# Camera.net
KiCad netlist of a schematic drawn in Altium Designer
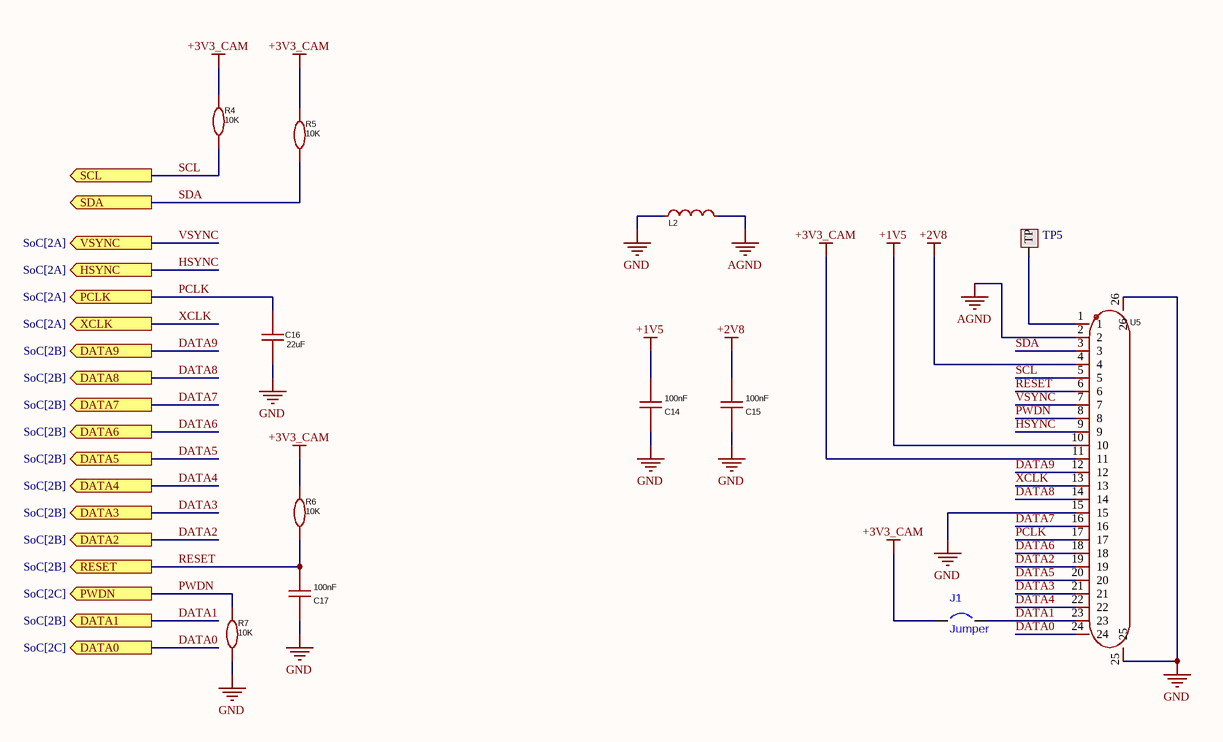
[diagram p0: Camera.SchDoc]

(export (version "E")
  (design (tool "Eeschema 10.0.6"))
  (components
    (comp (ref "C14")
      (value "100nF")
      (footprint "100nF SMD Ceramic 201")
      (description "10V 100nF X5R ±10% 0201 Multilayer Ceramic Capacitors MLCC - SMD/SMT ROHS")
      (fields
        (field (name "MANUFACTURER") "muRata(村田)")
        (field (name "MANUFACTURER PART") "GRM033R61A104KE84D")
      )
      (libsource (lib "Esp32 CAM SCH") (part "100nF SMD Ceramic 201"))
    )
    (comp (ref "C15")
      (value "100nF")
      (footprint "100nF SMD Ceramic 201")
      (description "10V 100nF X5R ±10% 0201 Multilayer Ceramic Capacitors MLCC - SMD/SMT ROHS")
      (fields
        (field (name "MANUFACTURER") "muRata(村田)")
        (field (name "MANUFACTURER PART") "GRM033R61A104KE84D")
      )
      (libsource (lib "Esp32 CAM SCH") (part "100nF SMD Ceramic 201"))
    )
    (comp (ref "C16")
      (value "22uF")
      (footprint "22uF SMD Ceramic 1210")
      (description "10V 22uF X7R ±10% 1210 Multilayer Ceramic Capacitors MLCC - SMD/SMT ROHS")
      (fields
        (field (name "MANUFACTURER") "KEMET(基美)")
        (field (name "MANUFACTURER PART") "C1210C226K8RACAUTO")
      )
      (libsource (lib "Esp32 CAM SCH") (part "22uF SMD Ceramic 1210"))
    )
    (comp (ref "C17")
      (value "100nF")
      (footprint "100nF SMD Ceramic 201")
      (description "10V 100nF X5R ±10% 0201 Multilayer Ceramic Capacitors MLCC - SMD/SMT ROHS")
      (fields
        (field (name "MANUFACTURER") "muRata(村田)")
        (field (name "MANUFACTURER PART") "GRM033R61A104KE84D")
      )
      (libsource (lib "Esp32 CAM SCH") (part "100nF SMD Ceramic 201"))
    )
    (comp (ref "J1")
      (value "Jumper")
      (footprint "PAD-JUMPER-2")
      (description "SMD JUMPER")
      (libsource (lib "Esp32 CAM SCH") (part "JUMPER SOLDER BRIDGE"))
    )
    (comp (ref "L2")
      (value "BLM15AG601SN1D")
      (footprint "Ferrite")
      (description "520mΩ ±25% 600Ω@100MHz 0402 Ferrite Beads ROHS")
      (fields (field (name "MANUFACTURER") "muRata(村田)") (field (name "TOLERANCE") "±25%"))
      (libsource (lib "Esp32 CAM SCH") (part "BLM15AG601SN1D"))
    )
    (comp (ref "R4")
      (value "10K")
      (footprint "10K SMD Ceramic 201")
      (description "50mW Thick Film Resistors 25V ±1% ±200ppm/℃ 10kΩ 0201 Chip Resistor - Surface Mount ROHS")
      (fields (field (name "MANUFACTURER") "YAGEO(国巨)") (field (name "MANUFACTURER PART") "AF0201FR-0710KL"))
      (libsource (lib "Esp32 CAM SCH") (part "10K SMD Ceramic 201"))
    )
    (comp (ref "R5")
      (value "10K")
      (footprint "10K SMD Ceramic 201")
      (description "50mW Thick Film Resistors 25V ±1% ±200ppm/℃ 10kΩ 0201 Chip Resistor - Surface Mount ROHS")
      (fields (field (name "MANUFACTURER") "YAGEO(国巨)") (field (name "MANUFACTURER PART") "AF0201FR-0710KL"))
      (libsource (lib "Esp32 CAM SCH") (part "10K SMD Ceramic 201"))
    )
    (comp (ref "R6")
      (value "10K")
      (footprint "10K SMD Ceramic 201")
      (description "50mW Thick Film Resistors 25V ±1% ±200ppm/℃ 10kΩ 0201 Chip Resistor - Surface Mount ROHS")
      (fields (field (name "MANUFACTURER") "YAGEO(国巨)") (field (name "MANUFACTURER PART") "AF0201FR-0710KL"))
      (libsource (lib "Esp32 CAM SCH") (part "10K SMD Ceramic 201"))
    )
    (comp (ref "R7")
      (value "10K")
      (footprint "10K SMD Ceramic 201")
      (description "50mW Thick Film Resistors 25V ±1% ±200ppm/℃ 10kΩ 0201 Chip Resistor - Surface Mount ROHS")
      (fields (field (name "MANUFACTURER") "YAGEO(国巨)") (field (name "MANUFACTURER PART") "AF0201FR-0710KL"))
      (libsource (lib "Esp32 CAM SCH") (part "10K SMD Ceramic 201"))
    )
    (comp (ref "TP5")
      (value "TEST POINT")
      (footprint "TESTPOINT")
      (libsource (lib "Esp32 CAM SCH") (part "TEST POINT"))
    )
    (comp (ref "U5")
      (value "FPC-05FB-24PH20")
      (footprint "Camera Connector")
      (fields (field (name "MANUFACTURER") "XUNPU(讯普)"))
      (libsource (lib "Esp32 CAM SCH") (part "Camera Connector"))
    )
  )
  (nets
    (net (code "1") (name "+1V5") (class "Default")
      (node (ref "C14") (pin "2") (pinfunction "2_2") (pintype "passive"))
      (node (ref "U5") (pin "10") (pinfunction "10_10") (pintype "passive"))
    )
    (net (code "2") (name "+2V8") (class "Default")
      (node (ref "C15") (pin "2") (pinfunction "2_2") (pintype "passive"))
      (node (ref "U5") (pin "4") (pinfunction "4_4") (pintype "passive"))
    )
    (net (code "3") (name "+3V3_CAM") (class "Default")
      (node (ref "J1") (pin "1") (pinfunction "1_1") (pintype "passive"))
      (node (ref "R4") (pin "2") (pinfunction "2_2") (pintype "passive"))
      (node (ref "R5") (pin "2") (pinfunction "2_2") (pintype "passive"))
      (node (ref "R6") (pin "2") (pinfunction "2_2") (pintype "passive"))
      (node (ref "U5") (pin "11") (pinfunction "11_11") (pintype "passive"))
    )
    (net (code "4") (name "/DATA0") (class "Default")
      (node (ref "U5") (pin "24") (pinfunction "24_24") (pintype "passive"))
    )
    (net (code "5") (name "/DATA1") (class "Default")
      (node (ref "J1") (pin "2") (pinfunction "2_2") (pintype "passive"))
      (node (ref "U5") (pin "23") (pinfunction "23_23") (pintype "passive"))
    )
    (net (code "6") (name "/DATA2") (class "Default")
      (node (ref "U5") (pin "19") (pinfunction "19_19") (pintype "passive"))
    )
    (net (code "7") (name "/DATA3") (class "Default")
      (node (ref "U5") (pin "21") (pinfunction "21_21") (pintype "passive"))
    )
    (net (code "8") (name "/DATA4") (class "Default")
      (node (ref "U5") (pin "22") (pinfunction "22_22") (pintype "passive"))
    )
    (net (code "9") (name "/DATA5") (class "Default")
      (node (ref "U5") (pin "20") (pinfunction "20_20") (pintype "passive"))
    )
    (net (code "10") (name "/DATA6") (class "Default")
      (node (ref "U5") (pin "18") (pinfunction "18_18") (pintype "passive"))
    )
    (net (code "11") (name "/DATA7") (class "Default")
      (node (ref "U5") (pin "16") (pinfunction "16_16") (pintype "passive"))
    )
    (net (code "12") (name "/DATA8") (class "Default")
      (node (ref "U5") (pin "14") (pinfunction "14_14") (pintype "passive"))
    )
    (net (code "13") (name "/DATA9") (class "Default")
      (node (ref "U5") (pin "12") (pinfunction "12_12") (pintype "passive"))
    )
    (net (code "14") (name "/HSYNC") (class "Default")
      (node (ref "U5") (pin "9") (pinfunction "9_9") (pintype "passive"))
    )
    (net (code "15") (name "/PCLK") (class "Default")
      (node (ref "C16") (pin "2") (pinfunction "2_2") (pintype "passive"))
      (node (ref "U5") (pin "17") (pinfunction "17_17") (pintype "passive"))
    )
    (net (code "16") (name "/PWDN") (class "Default")
      (node (ref "R7") (pin "2") (pinfunction "2_2") (pintype "passive"))
      (node (ref "U5") (pin "8") (pinfunction "8_8") (pintype "passive"))
    )
    (net (code "17") (name "/RESET") (class "Default")
      (node (ref "C17") (pin "2") (pinfunction "2_2") (pintype "passive"))
      (node (ref "R6") (pin "1") (pinfunction "1_1") (pintype "passive"))
      (node (ref "U5") (pin "6") (pinfunction "6_6") (pintype "passive"))
    )
    (net (code "18") (name "/SCL") (class "Default")
      (node (ref "R4") (pin "1") (pinfunction "1_1") (pintype "passive"))
      (node (ref "U5") (pin "5") (pinfunction "5_5") (pintype "passive"))
    )
    (net (code "19") (name "/SDA") (class "Default")
      (node (ref "R5") (pin "1") (pinfunction "1_1") (pintype "passive"))
      (node (ref "U5") (pin "3") (pinfunction "3_3") (pintype "passive"))
    )
    (net (code "20") (name "/VSYNC") (class "Default")
      (node (ref "U5") (pin "7") (pinfunction "7_7") (pintype "passive"))
    )
    (net (code "21") (name "/XCLK") (class "Default")
      (node (ref "U5") (pin "13") (pinfunction "13_13") (pintype "passive"))
    )
    (net (code "22") (name "AGND") (class "Default")
      (node (ref "L2") (pin "2") (pinfunction "2_2") (pintype "passive"))
      (node (ref "U5") (pin "2") (pinfunction "2_2") (pintype "passive"))
    )
    (net (code "23") (name "GND") (class "Default")
      (node (ref "C14") (pin "1") (pinfunction "1_1") (pintype "passive"))
      (node (ref "C15") (pin "1") (pinfunction "1_1") (pintype "passive"))
      (node (ref "C16") (pin "1") (pinfunction "1_1") (pintype "passive"))
      (node (ref "C17") (pin "1") (pinfunction "1_1") (pintype "passive"))
      (node (ref "L2") (pin "1") (pinfunction "1_1") (pintype "passive"))
      (node (ref "R7") (pin "1") (pinfunction "1_1") (pintype "passive"))
      (node (ref "U5") (pin "15") (pinfunction "15_15") (pintype "passive"))
      (node (ref "U5") (pin "25") (pinfunction "25_25") (pintype "passive"))
      (node (ref "U5") (pin "26") (pinfunction "26_26") (pintype "passive"))
    )
    (net (code "24") (name "Net-(TP5-TP)") (class "Default")
      (node (ref "TP5") (pin "1") (pinfunction "TP_1") (pintype "passive"))
      (node (ref "U5") (pin "1") (pinfunction "1_1") (pintype "passive"))
    )
  )
)
